# Ch_trig.net
KiCad netlist of a schematic drawn in Altium Designer
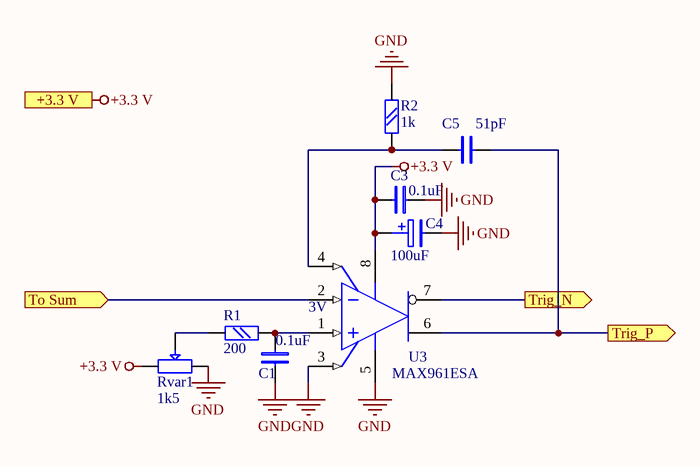
[diagram p0: Ch_trig.SchDoc]

(export (version "E")
  (design (tool "Eeschema 10.0.6"))
  (components
    (comp (ref "C1") (value "0.1uF") (footprint "chip0805") (libsource (lib "vDevice") (part "C")))
    (comp (ref "C3") (value "0.1uF") (footprint "chip0805") (libsource (lib "vDevice") (part "C")))
    (comp (ref "C4") (value "100uF") (footprint "CEL-SMD300") (libsource (lib "vDevice") (part "C POL")))
    (comp (ref "C5") (value "51pF") (footprint "chip0805") (libsource (lib "vDevice") (part "C")))
    (comp (ref "R1") (value "200") (footprint "chip0805") (libsource (lib "vDevice") (part "R")))
    (comp (ref "R2") (value "1k") (footprint "chip0805") (libsource (lib "vDevice") (part "R")))
    (comp (ref "Rvar1") (value "1k5") (footprint "RVAR4") (libsource (lib "vDevice") (part "R VAR")))
    (comp (ref "U3")
      (value "MAX961ESA")
      (footprint "NSO8_N")
      (description "Single Ultra-High-Speed, +3V/+5V, Beyond-the-Rails Comparator")
      (fields (field (name "PUBLISHER") "Altium Limited"))
      (libsource (lib "Maxim Analog Comparator") (part "MAX961ESA"))
    )
  )
  (nets
    (net (code "1") (name "+3.3 V") (class "Default")
      (node (ref "C3") (pin "2") (pinfunction "2_2") (pintype "passive"))
      (node (ref "C4") (pin "+") (pinfunction "+_+") (pintype "passive"))
      (node (ref "Rvar1") (pin "1") (pinfunction "1_1") (pintype "passive"))
      (node (ref "U3") (pin "8") (pinfunction "V+_8") (pintype "power_in"))
    )
    (net (code "2") (name "/To Sum") (class "Default")
      (node (ref "U3") (pin "2") (pinfunction "IN-_2") (pintype "input"))
    )
    (net (code "3") (name "/Trig_N") (class "Default")
      (node (ref "U3") (pin "7") (pinfunction "~{Q}_7") (pintype "tri_state"))
    )
    (net (code "4") (name "/Trig_P") (class "Default")
      (node (ref "C5") (pin "2") (pinfunction "2_2") (pintype "passive"))
      (node (ref "U3") (pin "6") (pinfunction "Q_6") (pintype "tri_state"))
    )
    (net (code "5") (name "GND") (class "Default")
      (node (ref "C1") (pin "1") (pinfunction "1_1") (pintype "passive"))
      (node (ref "C3") (pin "1") (pinfunction "1_1") (pintype "passive"))
      (node (ref "C4") (pin "-") (pinfunction "-_-") (pintype "passive"))
      (node (ref "R2") (pin "2") (pinfunction "2_2") (pintype "passive"))
      (node (ref "Rvar1") (pin "3") (pinfunction "3_3") (pintype "passive"))
      (node (ref "U3") (pin "3") (pinfunction "SHDN_3") (pintype "input"))
      (node (ref "U3") (pin "5") (pinfunction "GND_5") (pintype "power_in"))
    )
    (net (code "6") (name "Net-(R1-Pad1)") (class "Default")
      (node (ref "R1") (pin "1") (pinfunction "1_1") (pintype "passive"))
      (node (ref "Rvar1") (pin "2") (pinfunction "2_2") (pintype "passive"))
    )
    (net (code "7") (name "Net-(U3-IN+)") (class "Default")
      (node (ref "C1") (pin "2") (pinfunction "2_2") (pintype "passive"))
      (node (ref "R1") (pin "2") (pinfunction "2_2") (pintype "passive"))
      (node (ref "U3") (pin "1") (pinfunction "IN+_1") (pintype "input"))
    )
    (net (code "8") (name "Net-(U3-LE)") (class "Default")
      (node (ref "C5") (pin "1") (pinfunction "1_1") (pintype "passive"))
      (node (ref "R2") (pin "1") (pinfunction "1_1") (pintype "passive"))
      (node (ref "U3") (pin "4") (pinfunction "LE_4") (pintype "input"))
    )
  )
)
